# FPGA_Bank.net
KiCad netlist of a schematic drawn in Altium Designer
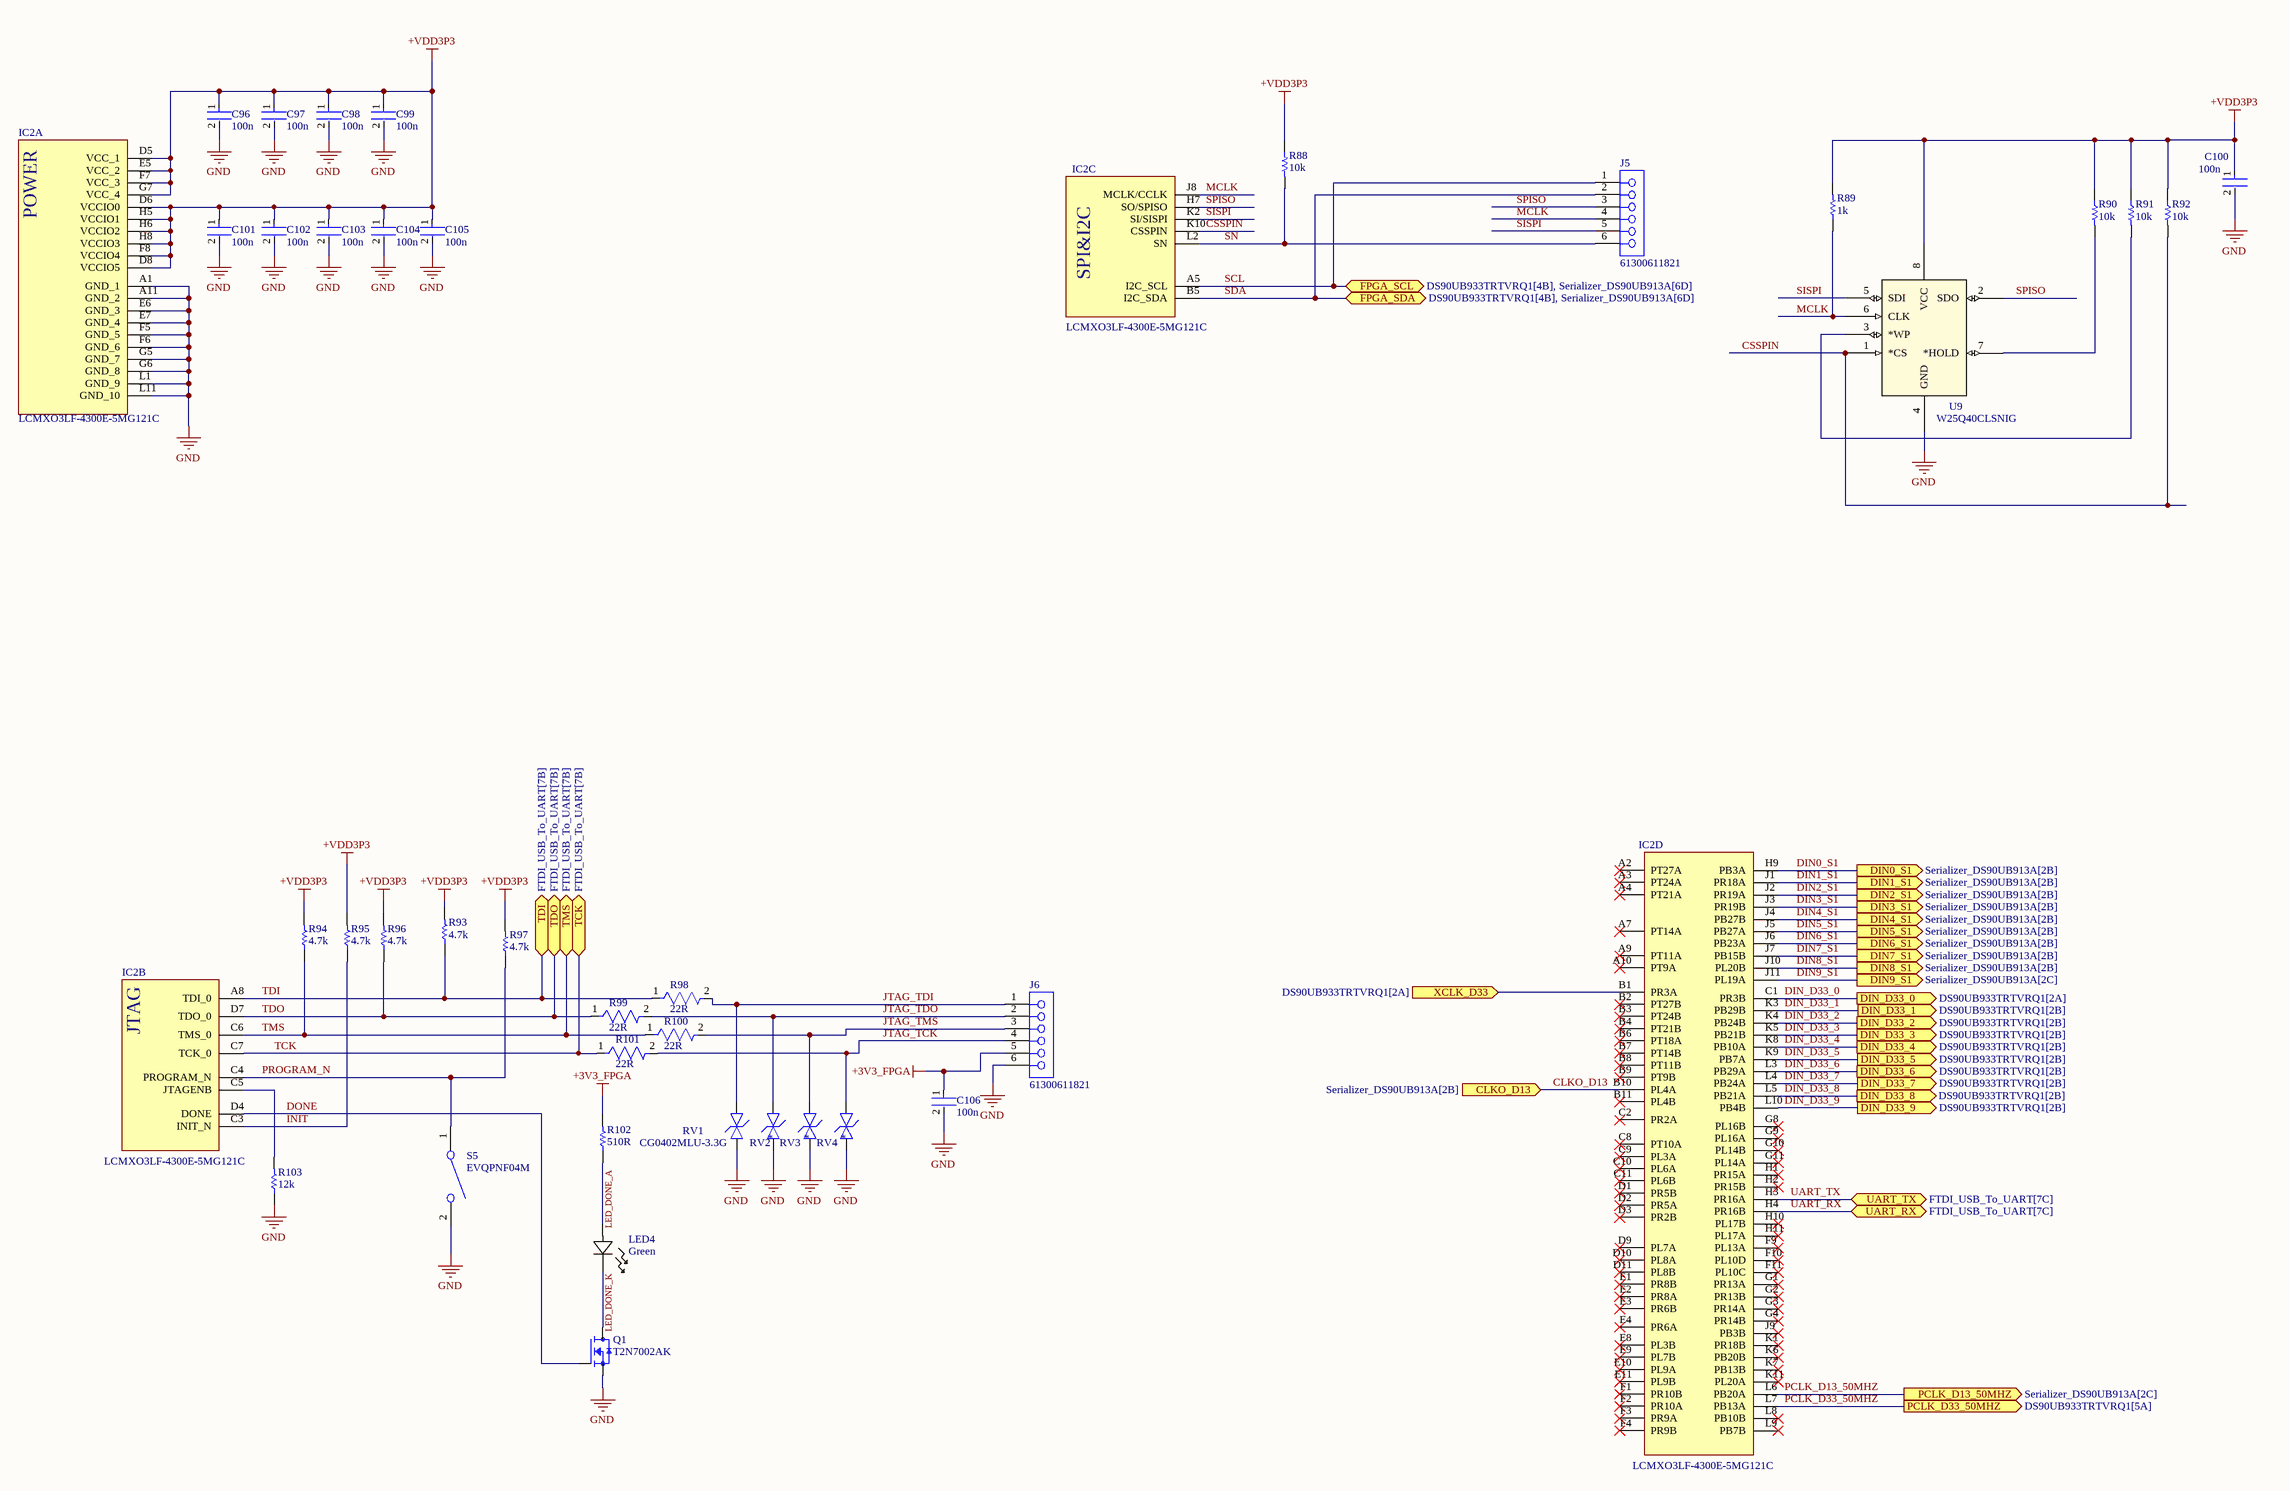
[diagram p0: FPGA_Bank.SchDoc]

(export (version "E")
  (design (tool "Eeschema 10.0.6"))
  (components
    (comp (ref "C96")
      (value "100n")
      (footprint "FP-CL278-IPC_C")
      (description "Cap Ceramic 100nF 25V X5R ±10% SMD 0402 +85°C Paper T/R")
      (fields (field (name "VOLTAGE") "25V") (field (name "TOLERANCE") "10%"))
      (libsource (lib "Altium Content Vault") (part "b4654b650e69147ec39a6b967a45e02"))
    )
    (comp (ref "C97")
      (value "100n")
      (footprint "FP-CL278-IPC_C")
      (description "Cap Ceramic 100nF 25V X5R ±10% SMD 0402 +85°C Paper T/R")
      (fields (field (name "VOLTAGE") "25V") (field (name "TOLERANCE") "10%"))
      (libsource (lib "Altium Content Vault") (part "b4654b650e69147ec39a6b967a45e02"))
    )
    (comp (ref "C98")
      (value "100n")
      (footprint "FP-CL278-IPC_C")
      (description "Cap Ceramic 100nF 25V X5R ±10% SMD 0402 +85°C Paper T/R")
      (fields (field (name "VOLTAGE") "25V") (field (name "TOLERANCE") "10%"))
      (libsource (lib "Altium Content Vault") (part "b4654b650e69147ec39a6b967a45e02"))
    )
    (comp (ref "C99")
      (value "100n")
      (footprint "FP-CL278-IPC_C")
      (description "Cap Ceramic 100nF 25V X5R ±10% SMD 0402 +85°C Paper T/R")
      (fields (field (name "VOLTAGE") "25V") (field (name "TOLERANCE") "10%"))
      (libsource (lib "Altium Content Vault") (part "b4654b650e69147ec39a6b967a45e02"))
    )
    (comp (ref "C100")
      (value "100n")
      (footprint "FP-CL278-IPC_C")
      (description "Cap Ceramic 100nF 25V X5R ±10% SMD 0402 +85°C Paper T/R")
      (fields (field (name "VOLTAGE") "25V") (field (name "TOLERANCE") "10%"))
      (libsource (lib "Altium Content Vault") (part "b4654b650e69147ec39a6b967a45e02"))
    )
    (comp (ref "C101")
      (value "100n")
      (footprint "FP-CL278-IPC_C")
      (description "Cap Ceramic 100nF 25V X5R ±10% SMD 0402 +85°C Paper T/R")
      (fields (field (name "VOLTAGE") "25V") (field (name "TOLERANCE") "10%"))
      (libsource (lib "Altium Content Vault") (part "b4654b650e69147ec39a6b967a45e02"))
    )
    (comp (ref "C102")
      (value "100n")
      (footprint "FP-CL278-IPC_C")
      (description "Cap Ceramic 100nF 25V X5R ±10% SMD 0402 +85°C Paper T/R")
      (fields (field (name "VOLTAGE") "25V") (field (name "TOLERANCE") "10%"))
      (libsource (lib "Altium Content Vault") (part "b4654b650e69147ec39a6b967a45e02"))
    )
    (comp (ref "C103")
      (value "100n")
      (footprint "FP-CL278-IPC_C")
      (description "Cap Ceramic 100nF 25V X5R ±10% SMD 0402 +85°C Paper T/R")
      (fields (field (name "VOLTAGE") "25V") (field (name "TOLERANCE") "10%"))
      (libsource (lib "Altium Content Vault") (part "b4654b650e69147ec39a6b967a45e02"))
    )
    (comp (ref "C104")
      (value "100n")
      (footprint "FP-CL278-IPC_C")
      (description "Cap Ceramic 100nF 25V X5R ±10% SMD 0402 +85°C Paper T/R")
      (fields (field (name "VOLTAGE") "25V") (field (name "TOLERANCE") "10%"))
      (libsource (lib "Altium Content Vault") (part "b4654b650e69147ec39a6b967a45e02"))
    )
    (comp (ref "C105")
      (value "100n")
      (footprint "FP-CL278-IPC_C")
      (description "Cap Ceramic 100nF 25V X5R ±10% SMD 0402 +85°C Paper T/R")
      (fields (field (name "VOLTAGE") "25V") (field (name "TOLERANCE") "10%"))
      (libsource (lib "Altium Content Vault") (part "b4654b650e69147ec39a6b967a45e02"))
    )
    (comp (ref "C106")
      (value "100n")
      (footprint "FP-CL278-IPC_C")
      (description "Cap Ceramic 100nF 25V X5R ±10% SMD 0402 +85°C Paper T/R")
      (fields (field (name "VOLTAGE") "25V") (field (name "TOLERANCE") "10%"))
      (libsource (lib "Altium Content Vault") (part "b4654b650e69147ec39a6b967a45e02"))
    )
    (comp (ref "IC2")
      (value "LCMXO3LF-4300E-5MG121C")
      (footprint "SerDes_Eval_Board_Footprints:CSFBGA-121_L6.0-W6.0-R11-C11-P0.50-TL")
      (description "FPGA IC")
      (fields (field (name "MOUSER PART NUMBER") "842-O3LF4300E5MG121C"))
      (libsource (lib "SerDes_Eval") (part "LCMXO3LF-4300E-5MG121C"))
    )
    (comp (ref "J5")
      (value "61300611821")
      (footprint "61300611821")
      (description "THT Vertical Socket Header WR-PHD, Pitch 2.54 mm, Single Row, 6 pins")
      (libsource (lib "Altium Content Vault") (part "Header_Female_1R_06P"))
    )
    (comp (ref "J6")
      (value "61300611821")
      (footprint "61300611821")
      (description "THT Vertical Socket Header WR-PHD, Pitch 2.54 mm, Single Row, 6 pins")
      (libsource (lib "Altium Content Vault") (part "Header_Female_1R_06P"))
    )
    (comp (ref "LED4")
      (value "Green")
      (footprint "LED_LTW-C193TS5_LTO")
      (description "No Description Available")
      (fields
        (field (name "MANUFACTURER_PART_NUMBER") "LTST-C191TGKT")
        (field (name "COPYRIGHT") "Copyright (C) 2025 Ultra Librarian. All rights reserved.")
      )
      (libsource (lib "SerDes_Eval") (part "LTST-C191TGKT"))
    )
    (comp (ref "Q1")
      (value "T2N7002AK")
      (footprint "SOT-23_TOS")
      (description "N-ch MOSFET, 60 V, 0.2 A, 3.9 Î©@10V, SOT-23(SOT23)")
      (fields (field (name "COPYRIGHT") "Copyright (C) 2025 Ultra Librarian. All rights reserved."))
      (libsource (lib "SerDes_Eval") (part "T2N7002AK"))
    )
    (comp (ref "R88")
      (value "10k")
      (footprint "RESC1005X40X25ML05T10")
      (fields (field (name "PART NUMBER") "CRCW040210K0FKEDHP") (field (name "MANUFACTURER") "Vishay Dale"))
      (libsource (lib "Altium Content Vault") (part "RES"))
    )
    (comp (ref "R89")
      (value "1k")
      (footprint "RESC1005X40X25NL05T05")
      (description "Chip Resistor, 1 KOhm, +/- 1%, 100 mW, -55 to 155 degC, 0402 (1005 Metric), RoHS, Tape and Reel")
      (fields (field (name "PARTNUMBER") "ERJ-2RKF1001X") (field (name "MANUFACTURER") "Basic Passives"))
      (libsource (lib "Altium Content Vault") (part "RES-2"))
    )
    (comp (ref "R90")
      (value "10k")
      (footprint "RESC1005X40X25ML05T10")
      (fields (field (name "PART NUMBER") "CRCW040210K0FKEDHP") (field (name "MANUFACTURER") "Vishay Dale"))
      (libsource (lib "Altium Content Vault") (part "RES"))
    )
    (comp (ref "R91")
      (value "10k")
      (footprint "RESC1005X40X25ML05T10")
      (fields (field (name "PART NUMBER") "CRCW040210K0FKEDHP") (field (name "MANUFACTURER") "Vishay Dale"))
      (libsource (lib "Altium Content Vault") (part "RES"))
    )
    (comp (ref "R92")
      (value "10k")
      (footprint "RESC1005X40X25ML05T10")
      (fields (field (name "PART NUMBER") "CRCW040210K0FKEDHP") (field (name "MANUFACTURER") "Vishay Dale"))
      (libsource (lib "Altium Content Vault") (part "RES"))
    )
    (comp (ref "R93")
      (value "4.7k")
      (footprint "RESC1005X40X25LL05T05")
      (description "Chip Resistor, 4.7 KOhm, +/- 1%, 0.1 W, -55 to 155 degC, 0402 (1005 Metric), RoHS, Tape and Reel")
      (fields (field (name "TOLERANCE") "1%") (field (name "PARTNUMBER") "ERJ-2RKF4701X"))
      (libsource (lib "Altium Content Vault") (part "RES-2"))
    )
    (comp (ref "R94")
      (value "4.7k")
      (footprint "RESC1005X40X25LL05T05")
      (description "Chip Resistor, 4.7 KOhm, +/- 1%, 0.1 W, -55 to 155 degC, 0402 (1005 Metric), RoHS, Tape and Reel")
      (fields (field (name "TOLERANCE") "1%") (field (name "PARTNUMBER") "ERJ-2RKF4701X"))
      (libsource (lib "Altium Content Vault") (part "RES-2"))
    )
    (comp (ref "R95")
      (value "4.7k")
      (footprint "RESC1005X40X25LL05T05")
      (description "Chip Resistor, 4.7 KOhm, +/- 1%, 0.1 W, -55 to 155 degC, 0402 (1005 Metric), RoHS, Tape and Reel")
      (fields (field (name "TOLERANCE") "1%") (field (name "PARTNUMBER") "ERJ-2RKF4701X"))
      (libsource (lib "Altium Content Vault") (part "RES-2"))
    )
    (comp (ref "R96")
      (value "4.7k")
      (footprint "RESC1005X40X25LL05T05")
      (description "Chip Resistor, 4.7 KOhm, +/- 1%, 0.1 W, -55 to 155 degC, 0402 (1005 Metric), RoHS, Tape and Reel")
      (fields (field (name "TOLERANCE") "1%") (field (name "PARTNUMBER") "ERJ-2RKF4701X"))
      (libsource (lib "Altium Content Vault") (part "RES-2"))
    )
    (comp (ref "R97")
      (value "4.7k")
      (footprint "RESC1005X40X25LL05T05")
      (description "Chip Resistor, 4.7 KOhm, +/- 1%, 0.1 W, -55 to 155 degC, 0402 (1005 Metric), RoHS, Tape and Reel")
      (fields (field (name "TOLERANCE") "1%") (field (name "PARTNUMBER") "ERJ-2RKF4701X"))
      (libsource (lib "Altium Content Vault") (part "RES-2"))
    )
    (comp (ref "R98")
      (value "22R")
      (footprint "FP-RC0402-0_4-MFG")
      (fields (field (name "TOLERANCE") "1%"))
      (libsource (lib "Altium Content Vault") (part "RC0402FR-0722RL"))
    )
    (comp (ref "R99")
      (value "22R")
      (footprint "FP-RC0402-0_4-MFG")
      (fields (field (name "TOLERANCE") "1%"))
      (libsource (lib "Altium Content Vault") (part "RC0402FR-0722RL"))
    )
    (comp (ref "R100")
      (value "22R")
      (footprint "FP-RC0402-0_4-MFG")
      (fields (field (name "TOLERANCE") "1%"))
      (libsource (lib "Altium Content Vault") (part "RC0402FR-0722RL"))
    )
    (comp (ref "R101")
      (value "22R")
      (footprint "FP-RC0402-0_4-MFG")
      (fields (field (name "TOLERANCE") "1%"))
      (libsource (lib "Altium Content Vault") (part "RC0402FR-0722RL"))
    )
    (comp (ref "R102")
      (value "510R")
      (footprint "RESC1005X40X25LL05T05")
      (fields (field (name "PART NUMBER") "CRCW0402510RFKED") (field (name "MANUFACTURER") "Vishay Dale"))
      (libsource (lib "Altium Content Vault") (part "RES"))
    )
    (comp (ref "R103")
      (value "12k")
      (footprint "RESC1005X40X25NL05T10")
      (fields (field (name "PART NUMBER") "RC0402FR-07100KL") (field (name "MANUFACTURER") "Yageo / Phycomp"))
      (libsource (lib "Altium Content Vault") (part "RES"))
    )
    (comp (ref "RV1")
      (value "CG0402MLU-3.3G")
      (footprint "SamacSys:VARC1005X41N")
      (description "Varistor")
      (fields (field (name "MOUSER PART NUMBER") "652-CG0402MLU-3.3G"))
      (libsource (lib "SerDes_Eval") (part "CG0402MLU-3.3G"))
    )
    (comp (ref "RV2")
      (value "*")
      (footprint "SamacSys:VARC1005X41N")
      (description "Varistor")
      (fields
        (field (name "MANUFACTURER_PART_NUMBER") "CG0402MLU-3.3G")
        (field (name "MOUSER PART NUMBER") "652-CG0402MLU-3.3G")
      )
      (libsource (lib "*") (part "CG0402MLU-3.3G"))
    )
    (comp (ref "RV3")
      (value "*")
      (footprint "SamacSys:VARC1005X41N")
      (description "Varistor")
      (fields
        (field (name "MANUFACTURER_PART_NUMBER") "CG0402MLU-3.3G")
        (field (name "MOUSER PART NUMBER") "652-CG0402MLU-3.3G")
      )
      (libsource (lib "*") (part "CG0402MLU-3.3G"))
    )
    (comp (ref "RV4")
      (value "*")
      (footprint "SamacSys:VARC1005X41N")
      (description "Varistor")
      (fields
        (field (name "MANUFACTURER_PART_NUMBER") "CG0402MLU-3.3G")
        (field (name "MOUSER PART NUMBER") "652-CG0402MLU-3.3G")
      )
      (libsource (lib "*") (part "CG0402MLU-3.3G"))
    )
    (comp (ref "S5")
      (value "EVQPNF04M")
      (footprint "SamacSys:EVQ5PN05K")
      (description "Switch")
      (libsource (lib "SerDes_Eval") (part "EVQPNF04M"))
    )
    (comp (ref "U9")
      (value "W25Q40CLSNIG")
      (footprint "WIN_SN-8_WIN")
      (description "No Description Available")
      (fields (field (name "COPYRIGHT") "Copyright (C) 2026 Ultra Librarian. All rights reserved."))
      (libsource (lib "SerDes_Eval") (part "W25Q40CLSNIG"))
    )
  )
  (nets
    (net (code "1") (name "+3V3_FPGA") (class "Default")
      (node (ref "C106") (pin "1") (pinfunction "1_1") (pintype "passive"))
      (node (ref "J6") (pin "5") (pinfunction "5_5") (pintype "passive"))
      (node (ref "R102") (pin "2") (pinfunction "2_2") (pintype "passive"))
    )
    (net (code "2") (name "+VDD3P3") (class "Default")
      (node (ref "C100") (pin "1") (pinfunction "1_1") (pintype "passive"))
      (node (ref "C101") (pin "1") (pinfunction "1_1") (pintype "passive"))
      (node (ref "C102") (pin "1") (pinfunction "1_1") (pintype "passive"))
      (node (ref "C103") (pin "1") (pinfunction "1_1") (pintype "passive"))
      (node (ref "C104") (pin "1") (pinfunction "1_1") (pintype "passive"))
      (node (ref "C105") (pin "1") (pinfunction "1_1") (pintype "passive"))
      (node (ref "C96") (pin "1") (pinfunction "1_1") (pintype "passive"))
      (node (ref "C97") (pin "1") (pinfunction "1_1") (pintype "passive"))
      (node (ref "C98") (pin "1") (pinfunction "1_1") (pintype "passive"))
      (node (ref "C99") (pin "1") (pinfunction "1_1") (pintype "passive"))
      (node (ref "IC2") (pin "D5") (pinfunction "VCC_1_D5") (pintype "passive"))
      (node (ref "IC2") (pin "D6") (pinfunction "VCCIO0_D6") (pintype "passive"))
      (node (ref "IC2") (pin "D8") (pinfunction "VCCIO5_D8") (pintype "passive"))
      (node (ref "IC2") (pin "E5") (pinfunction "VCC_2_E5") (pintype "passive"))
      (node (ref "IC2") (pin "F7") (pinfunction "VCC_3_F7") (pintype "passive"))
      (node (ref "IC2") (pin "F8") (pinfunction "VCCIO4_F8") (pintype "passive"))
      (node (ref "IC2") (pin "G7") (pinfunction "VCC_4_G7") (pintype "passive"))
      (node (ref "IC2") (pin "H5") (pinfunction "VCCIO1_H5") (pintype "passive"))
      (node (ref "IC2") (pin "H6") (pinfunction "VCCIO2_H6") (pintype "passive"))
      (node (ref "IC2") (pin "H8") (pinfunction "VCCIO3_H8") (pintype "passive"))
      (node (ref "R88") (pin "1") (pinfunction "1_1") (pintype "passive"))
      (node (ref "R89") (pin "2") (pinfunction "2_2") (pintype "passive"))
      (node (ref "R90") (pin "1") (pinfunction "1_1") (pintype "passive"))
      (node (ref "R91") (pin "1") (pinfunction "1_1") (pintype "passive"))
      (node (ref "R92") (pin "1") (pinfunction "1_1") (pintype "passive"))
      (node (ref "R93") (pin "2") (pinfunction "2_2") (pintype "passive"))
      (node (ref "R94") (pin "2") (pinfunction "2_2") (pintype "passive"))
      (node (ref "R95") (pin "2") (pinfunction "2_2") (pintype "passive"))
      (node (ref "R96") (pin "2") (pinfunction "2_2") (pintype "passive"))
      (node (ref "R97") (pin "2") (pinfunction "2_2") (pintype "passive"))
      (node (ref "U9") (pin "8") (pinfunction "VCC_8") (pintype "power_in"))
    )
    (net (code "3") (name "/CLKO_D13") (class "Default")
      (node (ref "IC2") (pin "B10") (pinfunction "PL4A_B10") (pintype "passive"))
    )
    (net (code "4") (name "/CSSPIN") (class "Default")
      (node (ref "IC2") (pin "K10") (pinfunction "CSSPIN_K10") (pintype "passive"))
      (node (ref "R92") (pin "2") (pinfunction "2_2") (pintype "passive"))
      (node (ref "U9") (pin "1") (pinfunction "*CS_1") (pintype "input"))
    )
    (net (code "5") (name "/DIN0_S1") (class "Default")
      (node (ref "IC2") (pin "H9") (pinfunction "PB3A_H9") (pintype "passive"))
    )
    (net (code "6") (name "/DIN1_S1") (class "Default")
      (node (ref "IC2") (pin "J1") (pinfunction "PR18A_J1") (pintype "passive"))
    )
    (net (code "7") (name "/DIN2_S1") (class "Default")
      (node (ref "IC2") (pin "J2") (pinfunction "PR19A_J2") (pintype "passive"))
    )
    (net (code "8") (name "/DIN3_S1") (class "Default")
      (node (ref "IC2") (pin "J3") (pinfunction "PR19B_J3") (pintype "passive"))
    )
    (net (code "9") (name "/DIN4_S1") (class "Default")
      (node (ref "IC2") (pin "J4") (pinfunction "PB27B_J4") (pintype "passive"))
    )
    (net (code "10") (name "/DIN5_S1") (class "Default")
      (node (ref "IC2") (pin "J5") (pinfunction "PB27A_J5") (pintype "passive"))
    )
    (net (code "11") (name "/DIN6_S1") (class "Default")
      (node (ref "IC2") (pin "J6") (pinfunction "PB23A_J6") (pintype "passive"))
    )
    (net (code "12") (name "/DIN7_S1") (class "Default")
      (node (ref "IC2") (pin "J7") (pinfunction "PB15B_J7") (pintype "passive"))
    )
    (net (code "13") (name "/DIN8_S1") (class "Default")
      (node (ref "IC2") (pin "J10") (pinfunction "PL20B_J10") (pintype "passive"))
    )
    (net (code "14") (name "/DIN9_S1") (class "Default")
      (node (ref "IC2") (pin "J11") (pinfunction "PL19A_J11") (pintype "passive"))
    )
    (net (code "15") (name "/DIN_D33_0") (class "Default")
      (node (ref "IC2") (pin "C1") (pinfunction "PR3B_C1") (pintype "passive"))
    )
    (net (code "16") (name "/DIN_D33_1") (class "Default")
      (node (ref "IC2") (pin "K3") (pinfunction "PB29B_K3") (pintype "passive"))
    )
    (net (code "17") (name "/DIN_D33_2") (class "Default")
      (node (ref "IC2") (pin "K4") (pinfunction "PB24B_K4") (pintype "passive"))
    )
    (net (code "18") (name "/DIN_D33_3") (class "Default")
      (node (ref "IC2") (pin "K5") (pinfunction "PB21B_K5") (pintype "passive"))
    )
    (net (code "19") (name "/DIN_D33_4") (class "Default")
      (node (ref "IC2") (pin "K8") (pinfunction "PB10A_K8") (pintype "passive"))
    )
    (net (code "20") (name "/DIN_D33_5") (class "Default")
      (node (ref "IC2") (pin "K9") (pinfunction "PB7A_K9") (pintype "passive"))
    )
    (net (code "21") (name "/DIN_D33_6") (class "Default")
      (node (ref "IC2") (pin "L3") (pinfunction "PB29A_L3") (pintype "passive"))
    )
    (net (code "22") (name "/DIN_D33_7") (class "Default")
      (node (ref "IC2") (pin "L4") (pinfunction "PB24A_L4") (pintype "passive"))
    )
    (net (code "23") (name "/DIN_D33_8") (class "Default")
      (node (ref "IC2") (pin "L5") (pinfunction "PB21A_L5") (pintype "passive"))
    )
    (net (code "24") (name "/DIN_D33_9") (class "Default")
      (node (ref "IC2") (pin "L10") (pinfunction "PB4B_L10") (pintype "passive"))
    )
    (net (code "25") (name "/DONE") (class "Default")
      (node (ref "IC2") (pin "D4") (pinfunction "DONE_D4") (pintype "passive"))
      (node (ref "Q1") (pin "1") (pinfunction "G_1") (pintype "passive"))
    )
    (net (code "26") (name "/INIT") (class "Default")
      (node (ref "IC2") (pin "C3") (pinfunction "INIT_N_C3") (pintype "passive"))
      (node (ref "R95") (pin "1") (pinfunction "1_1") (pintype "passive"))
    )
    (net (code "27") (name "/JTAG_TCK") (class "Default")
      (node (ref "J6") (pin "4") (pinfunction "4_4") (pintype "passive"))
      (node (ref "R101") (pin "2") (pinfunction "2_2") (pintype "passive"))
      (node (ref "RV4") (pin "K") (pinfunction "K_K") (pintype "passive"))
    )
    (net (code "28") (name "/JTAG_TDI") (class "Default")
      (node (ref "J6") (pin "1") (pinfunction "1_1") (pintype "passive"))
      (node (ref "R98") (pin "2") (pinfunction "2_2") (pintype "passive"))
      (node (ref "RV1") (pin "K") (pinfunction "K_K") (pintype "passive"))
    )
    (net (code "29") (name "/JTAG_TDO") (class "Default")
      (node (ref "J6") (pin "2") (pinfunction "2_2") (pintype "passive"))
      (node (ref "R99") (pin "2") (pinfunction "2_2") (pintype "passive"))
      (node (ref "RV2") (pin "K") (pinfunction "K_K") (pintype "passive"))
    )
    (net (code "30") (name "/JTAG_TMS") (class "Default")
      (node (ref "J6") (pin "3") (pinfunction "3_3") (pintype "passive"))
      (node (ref "R100") (pin "2") (pinfunction "2_2") (pintype "passive"))
      (node (ref "RV3") (pin "K") (pinfunction "K_K") (pintype "passive"))
    )
    (net (code "31") (name "/LED_DONE_A") (class "Default")
      (node (ref "LED4") (pin "2") (pinfunction "2_2") (pintype "passive"))
      (node (ref "R102") (pin "1") (pinfunction "1_1") (pintype "passive"))
    )
    (net (code "32") (name "/LED_DONE_K") (class "Default")
      (node (ref "LED4") (pin "1") (pinfunction "1_1") (pintype "passive"))
      (node (ref "Q1") (pin "3") (pinfunction "D_3") (pintype "passive"))
    )
    (net (code "33") (name "/MCLK") (class "Default")
      (node (ref "IC2") (pin "J8") (pinfunction "MCLK/CCLK_J8") (pintype "passive"))
      (node (ref "J5") (pin "4") (pinfunction "4_4") (pintype "passive"))
      (node (ref "R89") (pin "1") (pinfunction "1_1") (pintype "passive"))
      (node (ref "U9") (pin "6") (pinfunction "CLK_6") (pintype "input"))
    )
    (net (code "34") (name "/PCLK_D13_50MHZ") (class "Default")
      (node (ref "IC2") (pin "L6") (pinfunction "PB20A_L6") (pintype "passive"))
    )
    (net (code "35") (name "/PCLK_D33_50MHZ") (class "Default")
      (node (ref "IC2") (pin "L7") (pinfunction "PB13A_L7") (pintype "passive"))
    )
    (net (code "36") (name "/PROGRAM_N") (class "Default")
      (node (ref "IC2") (pin "C4") (pinfunction "PROGRAM_N_C4") (pintype "passive"))
      (node (ref "R97") (pin "1") (pinfunction "1_1") (pintype "passive"))
      (node (ref "S5") (pin "1") (pinfunction "COM_1") (pintype "passive"))
    )
    (net (code "37") (name "/SCL") (class "Default")
      (node (ref "IC2") (pin "A5") (pinfunction "I2C_SCL_A5") (pintype "passive"))
      (node (ref "J5") (pin "1") (pinfunction "1_1") (pintype "passive"))
    )
    (net (code "38") (name "/SDA") (class "Default")
      (node (ref "IC2") (pin "B5") (pinfunction "I2C_SDA_B5") (pintype "passive"))
      (node (ref "J5") (pin "2") (pinfunction "2_2") (pintype "passive"))
    )
    (net (code "39") (name "/SISPI") (class "Default")
      (node (ref "IC2") (pin "K2") (pinfunction "SI/SISPI_K2") (pintype "passive"))
      (node (ref "J5") (pin "5") (pinfunction "5_5") (pintype "passive"))
      (node (ref "U9") (pin "5") (pinfunction "SDI_5") (pintype "bidirectional"))
    )
    (net (code "40") (name "/SN") (class "Default")
      (node (ref "IC2") (pin "L2") (pinfunction "SN_L2") (pintype "passive"))
      (node (ref "J5") (pin "6") (pinfunction "6_6") (pintype "passive"))
      (node (ref "R88") (pin "2") (pinfunction "2_2") (pintype "passive"))
    )
    (net (code "41") (name "/SPISO") (class "Default")
      (node (ref "IC2") (pin "H7") (pinfunction "SO/SPISO_H7") (pintype "passive"))
      (node (ref "J5") (pin "3") (pinfunction "3_3") (pintype "passive"))
      (node (ref "U9") (pin "2") (pinfunction "SDO_2") (pintype "bidirectional"))
    )
    (net (code "42") (name "/TCK") (class "Default")
      (node (ref "IC2") (pin "C7") (pinfunction "TCK_0_C7") (pintype "passive"))
      (node (ref "R101") (pin "1") (pinfunction "1_1") (pintype "passive"))
    )
    (net (code "43") (name "/TDI") (class "Default")
      (node (ref "IC2") (pin "A8") (pinfunction "TDI_0_A8") (pintype "passive"))
      (node (ref "R93") (pin "1") (pinfunction "1_1") (pintype "passive"))
      (node (ref "R98") (pin "1") (pinfunction "1_1") (pintype "passive"))
    )
    (net (code "44") (name "/TDO") (class "Default")
      (node (ref "IC2") (pin "D7") (pinfunction "TDO_0_D7") (pintype "passive"))
      (node (ref "R96") (pin "1") (pinfunction "1_1") (pintype "passive"))
      (node (ref "R99") (pin "1") (pinfunction "1_1") (pintype "passive"))
    )
    (net (code "45") (name "/TMS") (class "Default")
      (node (ref "IC2") (pin "C6") (pinfunction "TMS_0_C6") (pintype "passive"))
      (node (ref "R100") (pin "1") (pinfunction "1_1") (pintype "passive"))
      (node (ref "R94") (pin "1") (pinfunction "1_1") (pintype "passive"))
    )
    (net (code "46") (name "/UART_RX") (class "Default")
      (node (ref "IC2") (pin "H4") (pinfunction "PR16B_H4") (pintype "passive"))
    )
    (net (code "47") (name "/UART_TX") (class "Default")
      (node (ref "IC2") (pin "H3") (pinfunction "PR16A_H3") (pintype "passive"))
    )
    (net (code "48") (name "/XCLK_D33") (class "Default")
      (node (ref "IC2") (pin "B1") (pinfunction "PR3A_B1") (pintype "passive"))
    )
    (net (code "49") (name "GND") (class "Default")
      (node (ref "C100") (pin "2") (pinfunction "2_2") (pintype "passive"))
      (node (ref "C101") (pin "2") (pinfunction "2_2") (pintype "passive"))
      (node (ref "C102") (pin "2") (pinfunction "2_2") (pintype "passive"))
      (node (ref "C103") (pin "2") (pinfunction "2_2") (pintype "passive"))
      (node (ref "C104") (pin "2") (pinfunction "2_2") (pintype "passive"))
      (node (ref "C105") (pin "2") (pinfunction "2_2") (pintype "passive"))
      (node (ref "C106") (pin "2") (pinfunction "2_2") (pintype "passive"))
      (node (ref "C96") (pin "2") (pinfunction "2_2") (pintype "passive"))
      (node (ref "C97") (pin "2") (pinfunction "2_2") (pintype "passive"))
      (node (ref "C98") (pin "2") (pinfunction "2_2") (pintype "passive"))
      (node (ref "C99") (pin "2") (pinfunction "2_2") (pintype "passive"))
      (node (ref "IC2") (pin "A1") (pinfunction "GND_1_A1") (pintype "passive"))
      (node (ref "IC2") (pin "A11") (pinfunction "GND_2_A11") (pintype "passive"))
      (node (ref "IC2") (pin "E6") (pinfunction "GND_3_E6") (pintype "passive"))
      (node (ref "IC2") (pin "E7") (pinfunction "GND_4_E7") (pintype "passive"))
      (node (ref "IC2") (pin "F5") (pinfunction "GND_5_F5") (pintype "passive"))
      (node (ref "IC2") (pin "F6") (pinfunction "GND_6_F6") (pintype "passive"))
      (node (ref "IC2") (pin "G5") (pinfunction "GND_7_G5") (pintype "passive"))
      (node (ref "IC2") (pin "G6") (pinfunction "GND_8_G6") (pintype "passive"))
      (node (ref "IC2") (pin "L1") (pinfunction "GND_9_L1") (pintype "passive"))
      (node (ref "IC2") (pin "L11") (pinfunction "GND_10_L11") (pintype "passive"))
      (node (ref "J6") (pin "6") (pinfunction "6_6") (pintype "passive"))
      (node (ref "Q1") (pin "2") (pinfunction "S_2") (pintype "passive"))
      (node (ref "R103") (pin "1") (pinfunction "1_1") (pintype "passive"))
      (node (ref "RV1") (pin "A") (pinfunction "A_A") (pintype "passive"))
      (node (ref "RV2") (pin "A") (pinfunction "A_A") (pintype "passive"))
      (node (ref "RV3") (pin "A") (pinfunction "A_A") (pintype "passive"))
      (node (ref "RV4") (pin "A") (pinfunction "A_A") (pintype "passive"))
      (node (ref "S5") (pin "2") (pinfunction "NO_2") (pintype "passive"))
      (node (ref "U9") (pin "4") (pinfunction "GND_4") (pintype "power_in"))
    )
    (net (code "50") (name "Net-(IC2B-JTAGENB)") (class "Default")
      (node (ref "IC2") (pin "C5") (pinfunction "JTAGENB_C5") (pintype "passive"))
      (node (ref "R103") (pin "2") (pinfunction "2_2") (pintype "passive"))
    )
    (net (code "51") (name "Net-(U9-*HOLD)") (class "Default")
      (node (ref "R90") (pin "2") (pinfunction "2_2") (pintype "passive"))
      (node (ref "U9") (pin "7") (pinfunction "*HOLD_7") (pintype "bidirectional"))
    )
    (net (code "52") (name "Net-(U9-*WP)") (class "Default")
      (node (ref "R91") (pin "2") (pinfunction "2_2") (pintype "passive"))
      (node (ref "U9") (pin "3") (pinfunction "*WP_3") (pintype "bidirectional"))
    )
    (net (code "53") (name "unconnected-(IC2D-PB3B-PadJ9)") (class "Default")
      (node (ref "IC2") (pin "J9") (pinfunction "PB3B_J9") (pintype "passive+no_connect"))
    )
    (net (code "54") (name "unconnected-(IC2D-PB7B-PadL9)") (class "Default")
      (node (ref "IC2") (pin "L9") (pinfunction "PB7B_L9") (pintype "passive+no_connect"))
    )
    (net (code "55") (name "unconnected-(IC2D-PB10B-PadL8)") (class "Default")
      (node (ref "IC2") (pin "L8") (pinfunction "PB10B_L8") (pintype "passive+no_connect"))
    )
    (net (code "56") (name "unconnected-(IC2D-PB13B-PadK7)") (class "Default")
      (node (ref "IC2") (pin "K7") (pinfunction "PB13B_K7") (pintype "passive+no_connect"))
    )
    (net (code "57") (name "unconnected-(IC2D-PB20B-PadK6)") (class "Default")
      (node (ref "IC2") (pin "K6") (pinfunction "PB20B_K6") (pintype "passive+no_connect"))
    )
    (net (code "58") (name "unconnected-(IC2D-PL3A-PadC9)") (class "Default")
      (node (ref "IC2") (pin "C9") (pinfunction "PL3A_C9") (pintype "passive+no_connect"))
    )
    (net (code "59") (name "unconnected-(IC2D-PL3B-PadE8)") (class "Default")
      (node (ref "IC2") (pin "E8") (pinfunction "PL3B_E8") (pintype "passive+no_connect"))
    )
    (net (code "60") (name "unconnected-(IC2D-PL4B-PadB11)") (class "Default")
      (node (ref "IC2") (pin "B11") (pinfunction "PL4B_B11") (pintype "passive+no_connect"))
    )
    (net (code "61") (name "unconnected-(IC2D-PL6A-PadC10)") (class "Default")
      (node (ref "IC2") (pin "C10") (pinfunction "PL6A_C10") (pintype "passive+no_connect"))
    )
    (net (code "62") (name "unconnected-(IC2D-PL6B-PadC11)") (class "Default")
      (node (ref "IC2") (pin "C11") (pinfunction "PL6B_C11") (pintype "passive+no_connect"))
    )
    (net (code "63") (name "unconnected-(IC2D-PL7A-PadD9)") (class "Default")
      (node (ref "IC2") (pin "D9") (pinfunction "PL7A_D9") (pintype "passive+no_connect"))
    )
    (net (code "64") (name "unconnected-(IC2D-PL7B-PadE9)") (class "Default")
      (node (ref "IC2") (pin "E9") (pinfunction "PL7B_E9") (pintype "passive+no_connect"))
    )
    (net (code "65") (name "unconnected-(IC2D-PL8A-PadD10)") (class "Default")
      (node (ref "IC2") (pin "D10") (pinfunction "PL8A_D10") (pintype "passive+no_connect"))
    )
    (net (code "66") (name "unconnected-(IC2D-PL8B-PadD11)") (class "Default")
      (node (ref "IC2") (pin "D11") (pinfunction "PL8B_D11") (pintype "passive+no_connect"))
    )
    (net (code "67") (name "unconnected-(IC2D-PL9A-PadE10)") (class "Default")
      (node (ref "IC2") (pin "E10") (pinfunction "PL9A_E10") (pintype "passive+no_connect"))
    )
    (net (code "68") (name "unconnected-(IC2D-PL9B-PadE11)") (class "Default")
      (node (ref "IC2") (pin "E11") (pinfunction "PL9B_E11") (pintype "passive+no_connect"))
    )
    (net (code "69") (name "unconnected-(IC2D-PL10C-PadF11)") (class "Default")
      (node (ref "IC2") (pin "F11") (pinfunction "PL10C_F11") (pintype "passive+no_connect"))
    )
    (net (code "70") (name "unconnected-(IC2D-PL10D-PadF10)") (class "Default")
      (node (ref "IC2") (pin "F10") (pinfunction "PL10D_F10") (pintype "passive+no_connect"))
    )
    (net (code "71") (name "unconnected-(IC2D-PL13A-PadF9)") (class "Default")
      (node (ref "IC2") (pin "F9") (pinfunction "PL13A_F9") (pintype "passive+no_connect"))
    )
    (net (code "72") (name "unconnected-(IC2D-PL14A-PadG11)") (class "Default")
      (node (ref "IC2") (pin "G11") (pinfunction "PL14A_G11") (pintype "passive+no_connect"))
    )
    (net (code "73") (name "unconnected-(IC2D-PL14B-PadG10)") (class "Default")
      (node (ref "IC2") (pin "G10") (pinfunction "PL14B_G10") (pintype "passive+no_connect"))
    )
    (net (code "74") (name "unconnected-(IC2D-PL16A-PadG9)") (class "Default")
      (node (ref "IC2") (pin "G9") (pinfunction "PL16A_G9") (pintype "passive+no_connect"))
    )
    (net (code "75") (name "unconnected-(IC2D-PL16B-PadG8)") (class "Default")
      (node (ref "IC2") (pin "G8") (pinfunction "PL16B_G8") (pintype "passive+no_connect"))
    )
    (net (code "76") (name "unconnected-(IC2D-PL17A-PadH11)") (class "Default")
      (node (ref "IC2") (pin "H11") (pinfunction "PL17A_H11") (pintype "passive+no_connect"))
    )
    (net (code "77") (name "unconnected-(IC2D-PL17B-PadH10)") (class "Default")
      (node (ref "IC2") (pin "H10") (pinfunction "PL17B_H10") (pintype "passive+no_connect"))
    )
    (net (code "78") (name "unconnected-(IC2D-PL20A-PadK11)") (class "Default")
      (node (ref "IC2") (pin "K11") (pinfunction "PL20A_K11") (pintype "passive+no_connect"))
    )
    (net (code "79") (name "unconnected-(IC2D-PR2A-PadC2)") (class "Default")
      (node (ref "IC2") (pin "C2") (pinfunction "PR2A_C2") (pintype "passive+no_connect"))
    )
    (net (code "80") (name "unconnected-(IC2D-PR2B-PadD3)") (class "Default")
      (node (ref "IC2") (pin "D3") (pinfunction "PR2B_D3") (pintype "passive+no_connect"))
    )
    (net (code "81") (name "unconnected-(IC2D-PR5A-PadD2)") (class "Default")
      (node (ref "IC2") (pin "D2") (pinfunction "PR5A_D2") (pintype "passive+no_connect"))
    )
    (net (code "82") (name "unconnected-(IC2D-PR5B-PadD1)") (class "Default")
      (node (ref "IC2") (pin "D1") (pinfunction "PR5B_D1") (pintype "passive+no_connect"))
    )
    (net (code "83") (name "unconnected-(IC2D-PR6A-PadE4)") (class "Default")
      (node (ref "IC2") (pin "E4") (pinfunction "PR6A_E4") (pintype "passive+no_connect"))
    )
    (net (code "84") (name "unconnected-(IC2D-PR6B-PadE3)") (class "Default")
      (node (ref "IC2") (pin "E3") (pinfunction "PR6B_E3") (pintype "passive+no_connect"))
    )
    (net (code "85") (name "unconnected-(IC2D-PR8A-PadE2)") (class "Default")
      (node (ref "IC2") (pin "E2") (pinfunction "PR8A_E2") (pintype "passive+no_connect"))
    )
    (net (code "86") (name "unconnected-(IC2D-PR8B-PadE1)") (class "Default")
      (node (ref "IC2") (pin "E1") (pinfunction "PR8B_E1") (pintype "passive+no_connect"))
    )
    (net (code "87") (name "unconnected-(IC2D-PR9A-PadF3)") (class "Default")
      (node (ref "IC2") (pin "F3") (pinfunction "PR9A_F3") (pintype "passive+no_connect"))
    )
    (net (code "88") (name "unconnected-(IC2D-PR9B-PadF4)") (class "Default")
      (node (ref "IC2") (pin "F4") (pinfunction "PR9B_F4") (pintype "passive+no_connect"))
    )
    (net (code "89") (name "unconnected-(IC2D-PR10A-PadF2)") (class "Default")
      (node (ref "IC2") (pin "F2") (pinfunction "PR10A_F2") (pintype "passive+no_connect"))
    )
    (net (code "90") (name "unconnected-(IC2D-PR10B-PadF1)") (class "Default")
      (node (ref "IC2") (pin "F1") (pinfunction "PR10B_F1") (pintype "passive+no_connect"))
    )
    (net (code "91") (name "unconnected-(IC2D-PR13A-PadG1)") (class "Default")
      (node (ref "IC2") (pin "G1") (pinfunction "PR13A_G1") (pintype "passive+no_connect"))
    )
    (net (code "92") (name "unconnected-(IC2D-PR13B-PadG2)") (class "Default")
      (node (ref "IC2") (pin "G2") (pinfunction "PR13B_G2") (pintype "passive+no_connect"))
    )
    (net (code "93") (name "unconnected-(IC2D-PR14A-PadG3)") (class "Default")
      (node (ref "IC2") (pin "G3") (pinfunction "PR14A_G3") (pintype "passive+no_connect"))
    )
    (net (code "94") (name "unconnected-(IC2D-PR14B-PadG4)") (class "Default")
      (node (ref "IC2") (pin "G4") (pinfunction "PR14B_G4") (pintype "passive+no_connect"))
    )
    (net (code "95") (name "unconnected-(IC2D-PR15A-PadH1)") (class "Default")
      (node (ref "IC2") (pin "H1") (pinfunction "PR15A_H1") (pintype "passive+no_connect"))
    )
    (net (code "96") (name "unconnected-(IC2D-PR15B-PadH2)") (class "Default")
      (node (ref "IC2") (pin "H2") (pinfunction "PR15B_H2") (pintype "passive+no_connect"))
    )
    (net (code "97") (name "unconnected-(IC2D-PR18B-PadK1)") (class "Default")
      (node (ref "IC2") (pin "K1") (pinfunction "PR18B_K1") (pintype "passive+no_connect"))
    )
    (net (code "98") (name "unconnected-(IC2D-PT9A-PadA10)") (class "Default")
      (node (ref "IC2") (pin "A10") (pinfunction "PT9A_A10") (pintype "passive+no_connect"))
    )
    (net (code "99") (name "unconnected-(IC2D-PT9B-PadB9)") (class "Default")
      (node (ref "IC2") (pin "B9") (pinfunction "PT9B_B9") (pintype "passive+no_connect"))
    )
    (net (code "100") (name "unconnected-(IC2D-PT10A-PadC8)") (class "Default")
      (node (ref "IC2") (pin "C8") (pinfunction "PT10A_C8") (pintype "passive+no_connect"))
    )
    (net (code "101") (name "unconnected-(IC2D-PT11A-PadA9)") (class "Default")
      (node (ref "IC2") (pin "A9") (pinfunction "PT11A_A9") (pintype "passive+no_connect"))
    )
    (net (code "102") (name "unconnected-(IC2D-PT11B-PadB8)") (class "Default")
      (node (ref "IC2") (pin "B8") (pinfunction "PT11B_B8") (pintype "passive+no_connect"))
    )
    (net (code "103") (name "unconnected-(IC2D-PT14A-PadA7)") (class "Default")
      (node (ref "IC2") (pin "A7") (pinfunction "PT14A_A7") (pintype "passive+no_connect"))
    )
    (net (code "104") (name "unconnected-(IC2D-PT14B-PadB7)") (class "Default")
      (node (ref "IC2") (pin "B7") (pinfunction "PT14B_B7") (pintype "passive+no_connect"))
    )
    (net (code "105") (name "unconnected-(IC2D-PT18A-PadB6)") (class "Default")
      (node (ref "IC2") (pin "B6") (pinfunction "PT18A_B6") (pintype "passive+no_connect"))
    )
    (net (code "106") (name "unconnected-(IC2D-PT21A-PadA4)") (class "Default")
      (node (ref "IC2") (pin "A4") (pinfunction "PT21A_A4") (pintype "passive+no_connect"))
    )
    (net (code "107") (name "unconnected-(IC2D-PT21B-PadB4)") (class "Default")
      (node (ref "IC2") (pin "B4") (pinfunction "PT21B_B4") (pintype "passive+no_connect"))
    )
    (net (code "108") (name "unconnected-(IC2D-PT24A-PadA3)") (class "Default")
      (node (ref "IC2") (pin "A3") (pinfunction "PT24A_A3") (pintype "passive+no_connect"))
    )
    (net (code "109") (name "unconnected-(IC2D-PT24B-PadB3)") (class "Default")
      (node (ref "IC2") (pin "B3") (pinfunction "PT24B_B3") (pintype "passive+no_connect"))
    )
    (net (code "110") (name "unconnected-(IC2D-PT27A-PadA2)") (class "Default")
      (node (ref "IC2") (pin "A2") (pinfunction "PT27A_A2") (pintype "passive+no_connect"))
    )
    (net (code "111") (name "unconnected-(IC2D-PT27B-PadB2)") (class "Default")
      (node (ref "IC2") (pin "B2") (pinfunction "PT27B_B2") (pintype "passive+no_connect"))
    )
  )
)
